# 20240709.net
KiCad netlist of a schematic drawn in EasyEDA Pro
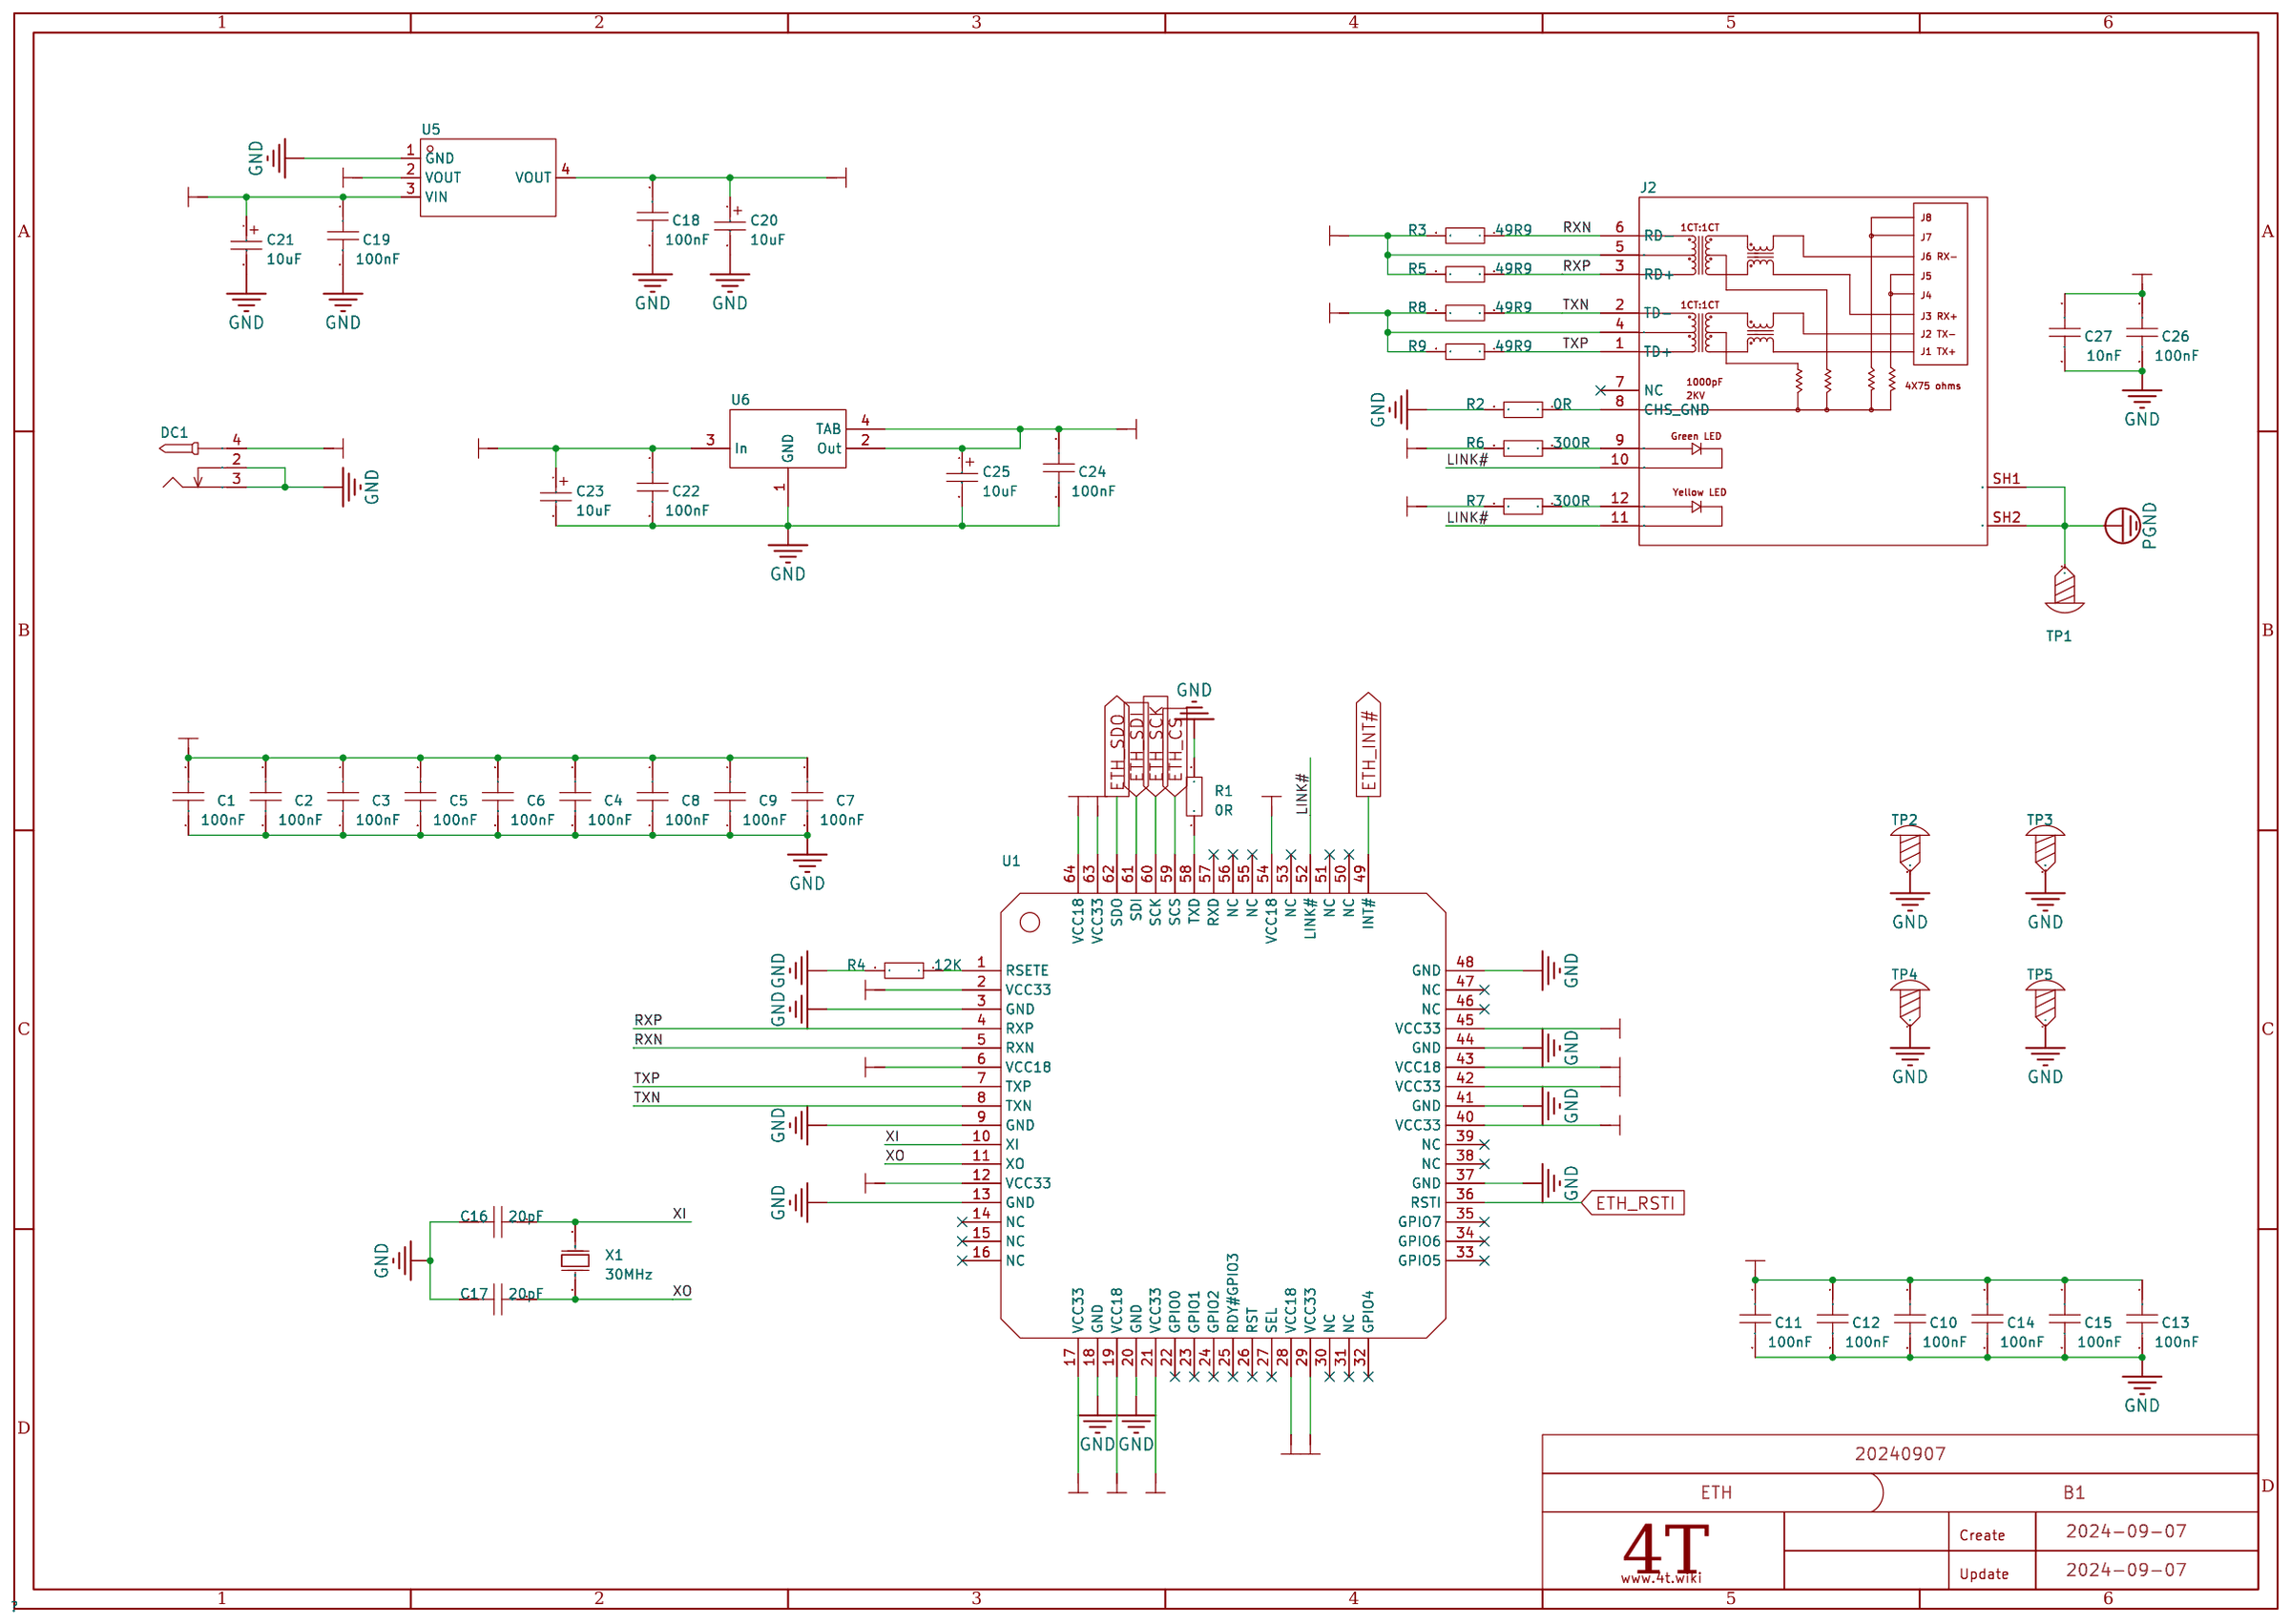
[diagram p0: ETH]
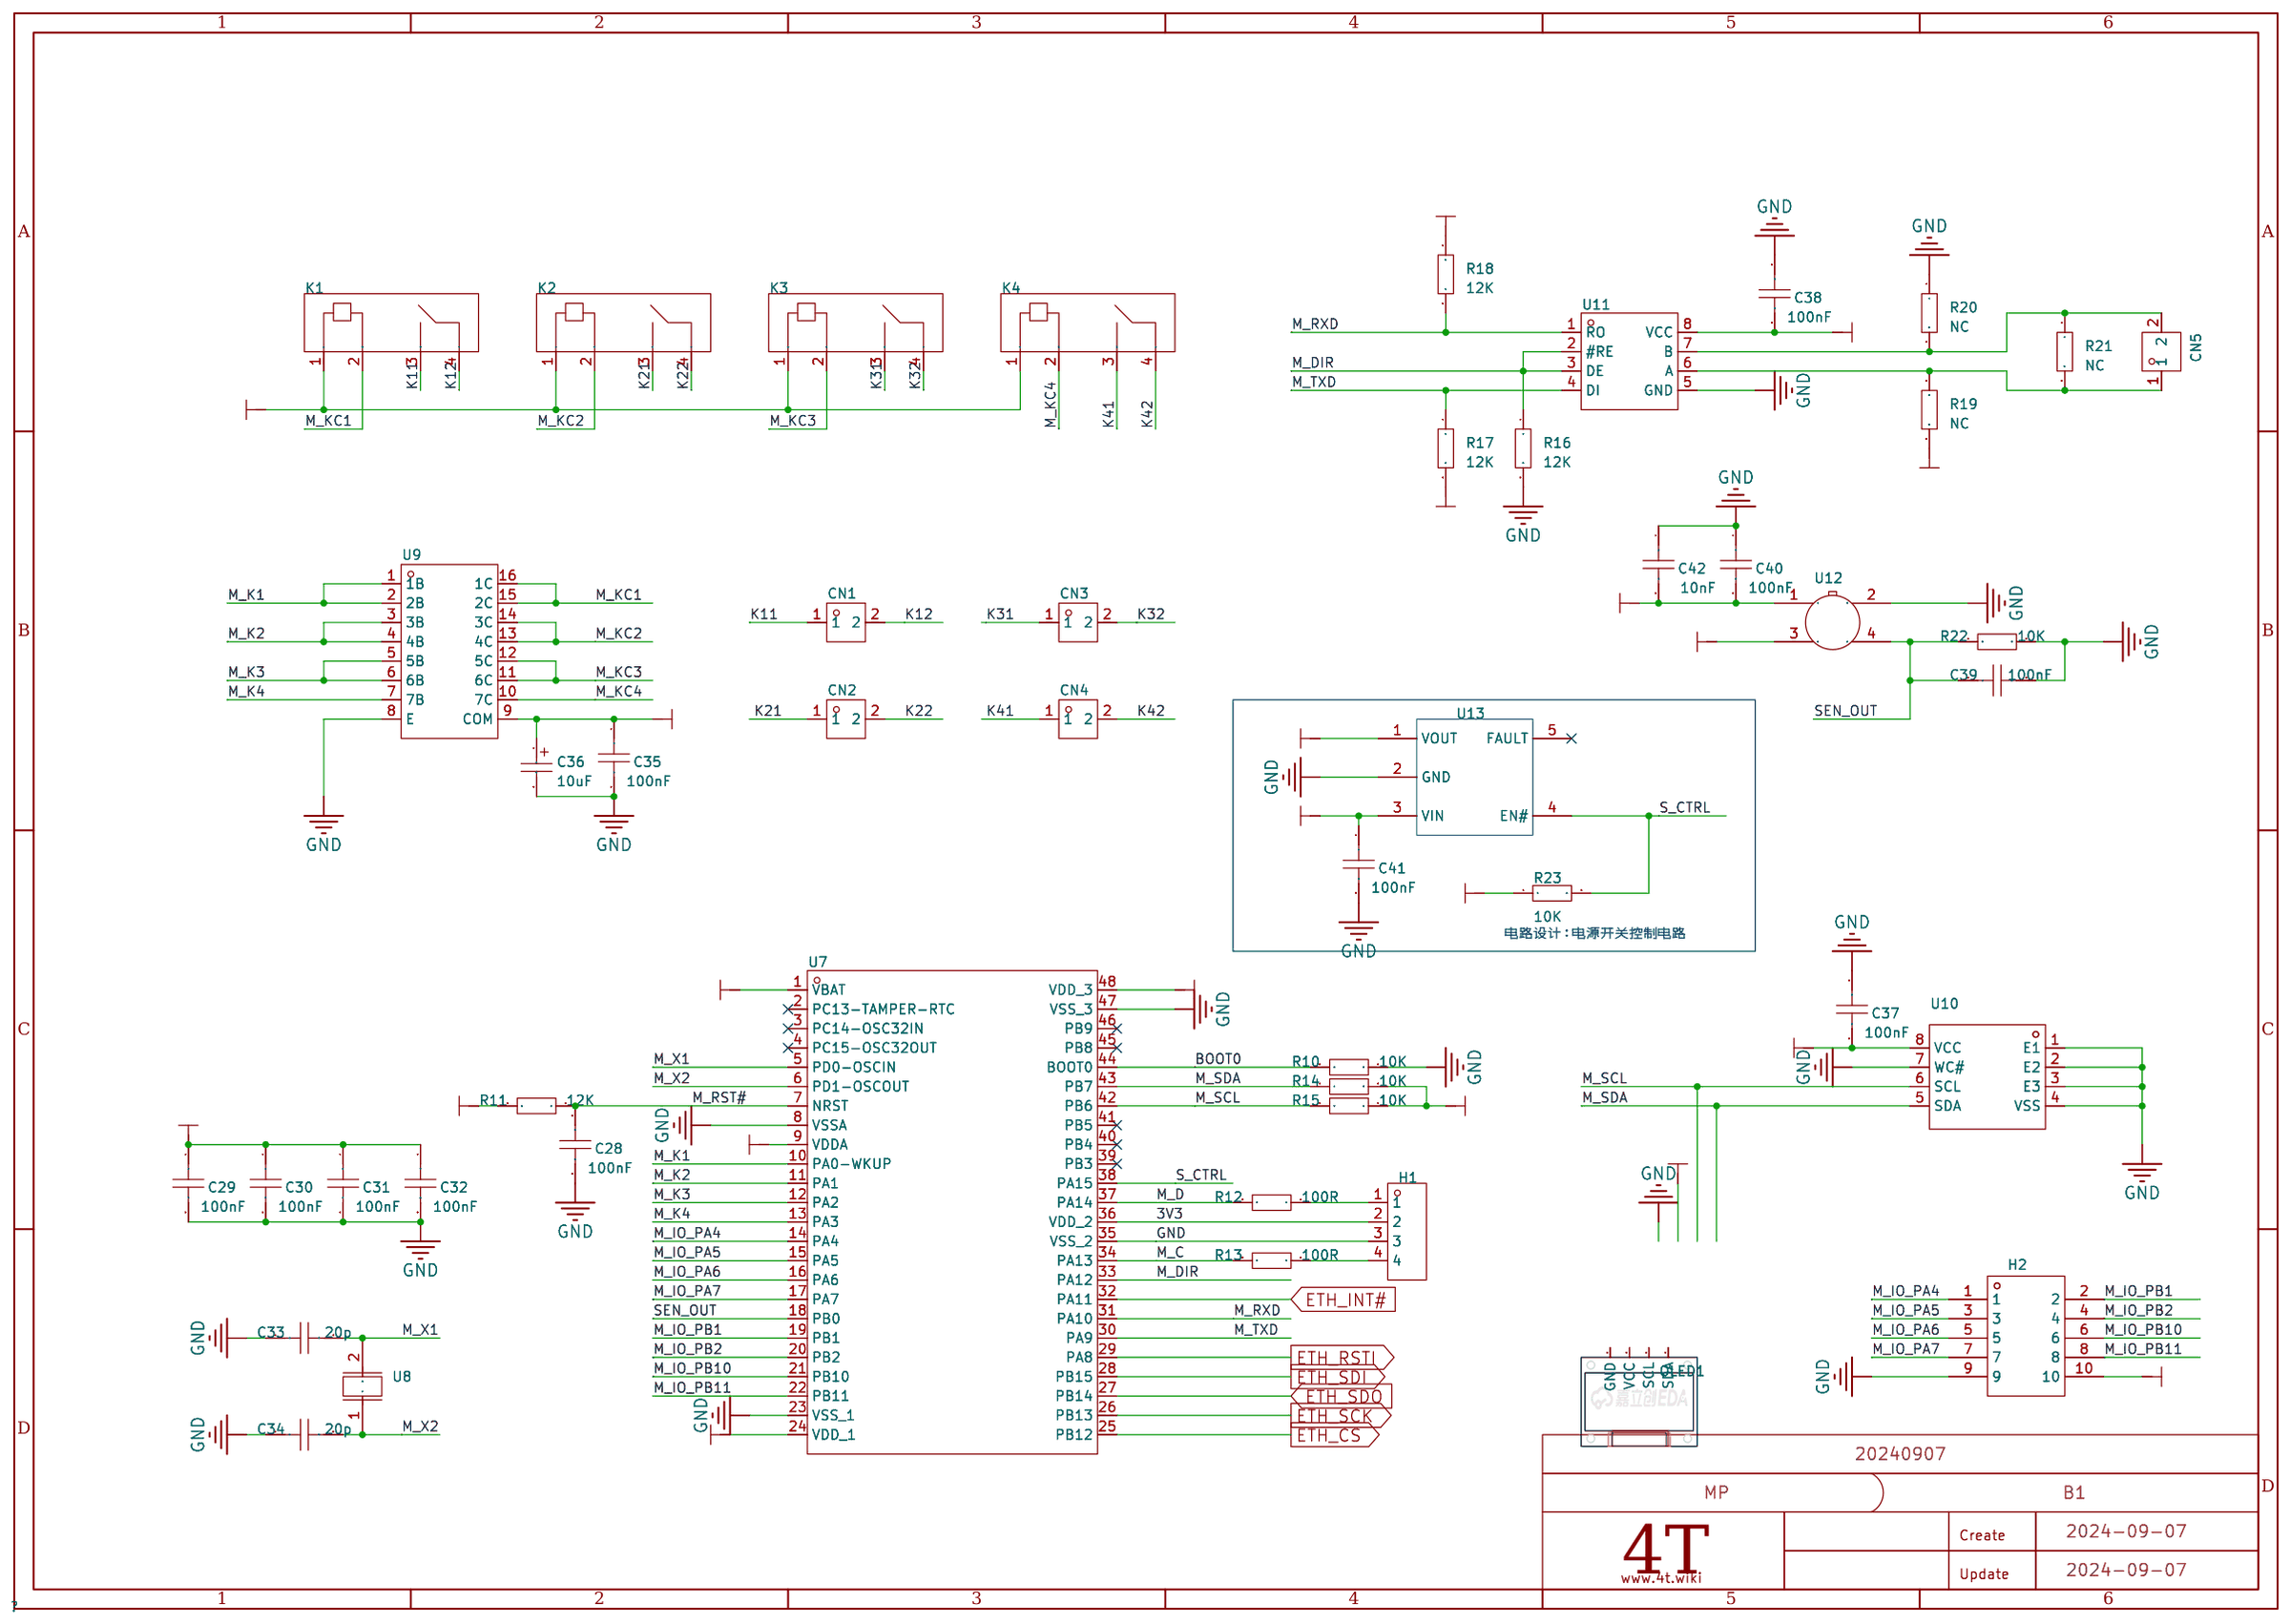
[diagram p1: MP]

(export (version "E")
  (design (tool "Eeschema 10.0.6"))
  (components
    (comp (ref "C1")
      (value "100nF")
      (footprint "easyedapro:C0805")
      (libsource (lib "easyedapro") (part "CapAcitance"))
    )
    (comp (ref "C2")
      (value "100nF")
      (footprint "easyedapro:C0805")
      (libsource (lib "easyedapro") (part "CapAcitance"))
    )
    (comp (ref "C3")
      (value "100nF")
      (footprint "easyedapro:C0805")
      (libsource (lib "easyedapro") (part "CapAcitance"))
    )
    (comp (ref "C4")
      (value "100nF")
      (footprint "easyedapro:C0805")
      (libsource (lib "easyedapro") (part "CapAcitance"))
    )
    (comp (ref "C5")
      (value "100nF")
      (footprint "easyedapro:C0805")
      (libsource (lib "easyedapro") (part "CapAcitance"))
    )
    (comp (ref "C6")
      (value "100nF")
      (footprint "easyedapro:C0805")
      (libsource (lib "easyedapro") (part "CapAcitance"))
    )
    (comp (ref "C7")
      (value "100nF")
      (footprint "easyedapro:C0805")
      (libsource (lib "easyedapro") (part "CapAcitance"))
    )
    (comp (ref "C8")
      (value "100nF")
      (footprint "easyedapro:C0805")
      (libsource (lib "easyedapro") (part "CapAcitance"))
    )
    (comp (ref "C9")
      (value "100nF")
      (footprint "easyedapro:C0805")
      (libsource (lib "easyedapro") (part "CapAcitance"))
    )
    (comp (ref "C10")
      (value "100nF")
      (footprint "easyedapro:C0805")
      (libsource (lib "easyedapro") (part "CapAcitance"))
    )
    (comp (ref "C11")
      (value "100nF")
      (footprint "easyedapro:C0805")
      (libsource (lib "easyedapro") (part "CapAcitance"))
    )
    (comp (ref "C12")
      (value "100nF")
      (footprint "easyedapro:C0805")
      (libsource (lib "easyedapro") (part "CapAcitance"))
    )
    (comp (ref "C13")
      (value "100nF")
      (footprint "easyedapro:C0805")
      (libsource (lib "easyedapro") (part "CapAcitance"))
    )
    (comp (ref "C14")
      (value "100nF")
      (footprint "easyedapro:C0805")
      (libsource (lib "easyedapro") (part "CapAcitance"))
    )
    (comp (ref "C15")
      (value "100nF")
      (footprint "easyedapro:C0805")
      (libsource (lib "easyedapro") (part "CapAcitance"))
    )
    (comp (ref "C16")
      (value "20pF")
      (footprint "easyedapro:C0805")
      (libsource (lib "easyedapro") (part "CapAcitance"))
    )
    (comp (ref "C17")
      (value "20pF")
      (footprint "easyedapro:C0805")
      (libsource (lib "easyedapro") (part "CapAcitance"))
    )
    (comp (ref "C18")
      (value "100nF")
      (footprint "easyedapro:C0805")
      (libsource (lib "easyedapro") (part "CapAcitance"))
    )
    (comp (ref "C19")
      (value "100nF")
      (footprint "easyedapro:C0805")
      (libsource (lib "easyedapro") (part "CapAcitance"))
    )
    (comp (ref "C20")
      (value "10uF")
      (footprint "easyedapro:C_Ele_SMD_3x5.4mm")
      (libsource (lib "easyedapro") (part "CAP"))
    )
    (comp (ref "C21")
      (value "10uF")
      (footprint "easyedapro:C_Ele_SMD_3x5.4mm")
      (libsource (lib "easyedapro") (part "CAP"))
    )
    (comp (ref "C22")
      (value "100nF")
      (footprint "easyedapro:C0805")
      (libsource (lib "easyedapro") (part "CapAcitance"))
    )
    (comp (ref "C23")
      (value "10uF")
      (footprint "easyedapro:C_Ele_SMD_3x5.4mm")
      (libsource (lib "easyedapro") (part "CAP"))
    )
    (comp (ref "C24")
      (value "100nF")
      (footprint "easyedapro:C0805")
      (libsource (lib "easyedapro") (part "CapAcitance"))
    )
    (comp (ref "C25")
      (value "10uF")
      (footprint "easyedapro:C_Ele_SMD_3x5.4mm")
      (libsource (lib "easyedapro") (part "CAP"))
    )
    (comp (ref "C26")
      (value "100nF")
      (footprint "easyedapro:C0805")
      (libsource (lib "easyedapro") (part "CapAcitance"))
    )
    (comp (ref "C27")
      (value "10nF")
      (footprint "easyedapro:C0805")
      (libsource (lib "easyedapro") (part "CapAcitance"))
    )
    (comp (ref "DC1")
      (value "~")
      (footprint "easyedapro:DC-2.0")
      (libsource (lib "easyedapro") (part "DC电源接口"))
    )
    (comp (ref "J2")
      (value "HY911105AE")
      (footprint "easyedapro:RJ45-TH_HR911105A")
      (description "连接器类型:RJ插座;USOC代码:RJ45;端口数量:1;等级:-;屏蔽:-;LED:-;")
      (fields (field (name "Manufacturer") "HANRUN(汉仁)"))
      (libsource (lib "easyedapro") (part "HY911105AE"))
    )
    (comp (ref "R1") (value "0R") (footprint "easyedapro:R0805") (libsource (lib "easyedapro") (part "电阻")))
    (comp (ref "R2") (value "0R") (footprint "easyedapro:R0805") (libsource (lib "easyedapro") (part "电阻")))
    (comp (ref "R3") (value "49R9") (footprint "easyedapro:R0805") (libsource (lib "easyedapro") (part "电阻")))
    (comp (ref "R4") (value "12K") (footprint "easyedapro:R0805") (libsource (lib "easyedapro") (part "电阻")))
    (comp (ref "R5") (value "49R9") (footprint "easyedapro:R0805") (libsource (lib "easyedapro") (part "电阻")))
    (comp (ref "R6") (value "300R") (footprint "easyedapro:R0805") (libsource (lib "easyedapro") (part "电阻")))
    (comp (ref "R7") (value "300R") (footprint "easyedapro:R0805") (libsource (lib "easyedapro") (part "电阻")))
    (comp (ref "R8") (value "49R9") (footprint "easyedapro:R0805") (libsource (lib "easyedapro") (part "电阻")))
    (comp (ref "R9") (value "49R9") (footprint "easyedapro:R0805") (libsource (lib "easyedapro") (part "电阻")))
    (comp (ref "TP1") (value "~") (footprint "easyedapro:M3螺丝") (libsource (lib "easyedapro") (part "螺丝孔")))
    (comp (ref "TP2") (value "~") (footprint "easyedapro:M3螺丝") (libsource (lib "easyedapro") (part "螺丝孔")))
    (comp (ref "TP3") (value "~") (footprint "easyedapro:M3螺丝") (libsource (lib "easyedapro") (part "螺丝孔")))
    (comp (ref "TP4") (value "~") (footprint "easyedapro:M3螺丝") (libsource (lib "easyedapro") (part "螺丝孔")))
    (comp (ref "TP5") (value "~") (footprint "easyedapro:M3螺丝") (libsource (lib "easyedapro") (part "螺丝孔")))
    (comp (ref "U1")
      (value "CH395Q")
      (footprint "easyedapro:LQFP-64_L10.0-W10.0-P0.50-LS12.0-BL")
      (description "应用功能:以太网控制器;通道数:-;接口类型:Parallel, SPI, UART;电源电压:1.65V~3.6V;电源电流:90mA;")
      (fields (field (name "Manufacturer") "WCH(南京沁恒)"))
      (libsource (lib "easyedapro") (part "CH395Q"))
    )
    (comp (ref "U5")
      (value "AMS1117-3.3")
      (footprint "easyedapro:SOT-223-3_L6.5-W3.4-P2.30-LS7.0-BR")
      (fields (field (name "Manufacturer") "AMS"))
      (libsource (lib "easyedapro") (part "AMS1117-3.3"))
    )
    (comp (ref "U6")
      (value "AMS1117-1.8")
      (footprint "easyedapro:SOT-223-4_L6.5-W3.5-P2.30-LS7.0-BR")
      (description "输出类型:固定;输出极性:正;输出通道数:1;最大输入电压:15V;输出电压:1.8V~1.8V;压差:1.3V@(1A);输出电流:1A;电源纹波抑制比(PSRR):75dB@(120Hz);")
      (fields (field (name "Manufacturer") "AMS"))
      (libsource (lib "easyedapro") (part "AMS1117-1.8"))
    )
    (comp (ref "X1")
      (value "30MHz")
      (footprint "easyedapro:OSC-SMD_L5.0-W3.2")
      (description "晶振类型:贴片无源晶振;频率:30MHz;频率公差:±10ppm;频率稳定度:±50ppm;负载电容:20pF;工作温度:-40°C~+85°C;")
      (fields (field (name "Manufacturer Part") "X503230MSB2GI") (field (name "Manufacturer") "YXC(扬兴晶振)"))
      (libsource (lib "easyedapro") (part "X503230MSB2GI"))
    )
    (comp (ref "C28")
      (value "100nF")
      (footprint "easyedapro:C0805")
      (libsource (lib "easyedapro") (part "CapAcitance"))
    )
    (comp (ref "C29")
      (value "100nF")
      (footprint "easyedapro:C0805")
      (libsource (lib "easyedapro") (part "CapAcitance"))
    )
    (comp (ref "C30")
      (value "100nF")
      (footprint "easyedapro:C0805")
      (libsource (lib "easyedapro") (part "CapAcitance"))
    )
    (comp (ref "C31")
      (value "100nF")
      (footprint "easyedapro:C0805")
      (libsource (lib "easyedapro") (part "CapAcitance"))
    )
    (comp (ref "C32")
      (value "100nF")
      (footprint "easyedapro:C0805")
      (libsource (lib "easyedapro") (part "CapAcitance"))
    )
    (comp (ref "C33")
      (value "20p")
      (footprint "easyedapro:C0805")
      (libsource (lib "easyedapro") (part "CapAcitance"))
    )
    (comp (ref "C34")
      (value "20p")
      (footprint "easyedapro:C0805")
      (libsource (lib "easyedapro") (part "CapAcitance"))
    )
    (comp (ref "C35")
      (value "100nF")
      (footprint "easyedapro:C0805")
      (libsource (lib "easyedapro") (part "CapAcitance"))
    )
    (comp (ref "C36")
      (value "10uF")
      (footprint "easyedapro:C_Ele_SMD_3x5.4mm")
      (libsource (lib "easyedapro") (part "CAP"))
    )
    (comp (ref "C37")
      (value "100nF")
      (footprint "easyedapro:C0805")
      (libsource (lib "easyedapro") (part "CapAcitance"))
    )
    (comp (ref "C38")
      (value "100nF")
      (footprint "easyedapro:C0805")
      (libsource (lib "easyedapro") (part "CapAcitance"))
    )
    (comp (ref "C39")
      (value "100nF")
      (footprint "easyedapro:C0805")
      (libsource (lib "easyedapro") (part "CapAcitance"))
    )
    (comp (ref "C40")
      (value "100nF")
      (footprint "easyedapro:C0805")
      (libsource (lib "easyedapro") (part "CapAcitance"))
    )
    (comp (ref "C41")
      (value "100nF")
      (footprint "easyedapro:C0805")
      (libsource (lib "easyedapro") (part "CapAcitance"))
    )
    (comp (ref "C42")
      (value "10nF")
      (footprint "easyedapro:C0805")
      (libsource (lib "easyedapro") (part "CapAcitance"))
    )
    (comp (ref "CN1")
      (value "KF128L-5.08-2P 蓝色")
      (footprint "easyedapro:TH_KF128L-5.08-2P")
      (libsource (lib "easyedapro") (part "KF128L-5.08-2P 蓝色"))
    )
    (comp (ref "CN2")
      (value "KF128L-5.08-2P 蓝色")
      (footprint "easyedapro:TH_KF128L-5.08-2P")
      (libsource (lib "easyedapro") (part "KF128L-5.08-2P 蓝色"))
    )
    (comp (ref "CN3")
      (value "KF128L-5.08-2P 蓝色")
      (footprint "easyedapro:TH_KF128L-5.08-2P")
      (libsource (lib "easyedapro") (part "KF128L-5.08-2P 蓝色"))
    )
    (comp (ref "CN4")
      (value "KF128L-5.08-2P 蓝色")
      (footprint "easyedapro:TH_KF128L-5.08-2P")
      (libsource (lib "easyedapro") (part "KF128L-5.08-2P 蓝色"))
    )
    (comp (ref "CN5")
      (value "KF128L-5.08-2P 蓝色")
      (footprint "easyedapro:TH_KF128L-5.08-2P")
      (libsource (lib "easyedapro") (part "KF128L-5.08-2P 蓝色"))
    )
    (comp (ref "H1")
      (value "~")
      (footprint "easyedapro:HDR-TH_4P-P2.54-V-F")
      (libsource (lib "easyedapro") (part "2.54-1*4P母"))
    )
    (comp (ref "H2")
      (value "~")
      (footprint "easyedapro:HDR-TH_10P-P2.54-V-M-R2-C5-S2.54")
      (libsource (lib "easyedapro") (part "HDR-M-2.54_2x5"))
    )
    (comp (ref "K1")
      (value "HF49FD/012-1H12")
      (footprint "easyedapro:RELAY-TH_HF49FD-XXX-1H12-XXX")
      (description "线圈电压:12V;线圈类型:非极化-单线圈;触点形式:一组常开:1A(单刀单掷-常开);最大切换电流:5A;触点材料:AgNi;")
      (fields (field (name "Manufacturer") "HF(宏发)"))
      (libsource (lib "easyedapro") (part "HF49FD/012-1H12"))
    )
    (comp (ref "K2")
      (value "HF49FD/012-1H12")
      (footprint "easyedapro:RELAY-TH_HF49FD-XXX-1H12-XXX")
      (description "线圈电压:12V;线圈类型:非极化-单线圈;触点形式:一组常开:1A(单刀单掷-常开);最大切换电流:5A;触点材料:AgNi;")
      (fields (field (name "Manufacturer") "HF(宏发)"))
      (libsource (lib "easyedapro") (part "HF49FD/012-1H12"))
    )
    (comp (ref "K3")
      (value "HF49FD/012-1H12")
      (footprint "easyedapro:RELAY-TH_HF49FD-XXX-1H12-XXX")
      (description "线圈电压:12V;线圈类型:非极化-单线圈;触点形式:一组常开:1A(单刀单掷-常开);最大切换电流:5A;触点材料:AgNi;")
      (fields (field (name "Manufacturer") "HF(宏发)"))
      (libsource (lib "easyedapro") (part "HF49FD/012-1H12"))
    )
    (comp (ref "K4")
      (value "HF49FD/012-1H12")
      (footprint "easyedapro:RELAY-TH_HF49FD-XXX-1H12-XXX")
      (description "线圈电压:12V;线圈类型:非极化-单线圈;触点形式:一组常开:1A(单刀单掷-常开);最大切换电流:5A;触点材料:AgNi;")
      (fields (field (name "Manufacturer") "HF(宏发)"))
      (libsource (lib "easyedapro") (part "HF49FD/012-1H12"))
    )
    (comp (ref "OLED1")
      (value "~")
      (footprint "easyedapro:0.96OLED_4P")
      (libsource (lib "easyedapro") (part "0.96OLED模块_4P"))
    )
    (comp (ref "R10") (value "10K") (footprint "easyedapro:R0805") (libsource (lib "easyedapro") (part "电阻")))
    (comp (ref "R11") (value "12K") (footprint "easyedapro:R0805") (libsource (lib "easyedapro") (part "电阻")))
    (comp (ref "R12")
      (value "100R")
      (footprint "easyedapro:R0805")
      (libsource (lib "easyedapro") (part "电阻"))
    )
    (comp (ref "R13")
      (value "100R")
      (footprint "easyedapro:R0805")
      (libsource (lib "easyedapro") (part "电阻"))
    )
    (comp (ref "R14") (value "10K") (footprint "easyedapro:R0805") (libsource (lib "easyedapro") (part "电阻")))
    (comp (ref "R15") (value "10K") (footprint "easyedapro:R0805") (libsource (lib "easyedapro") (part "电阻")))
    (comp (ref "R16") (value "12K") (footprint "easyedapro:R0805") (libsource (lib "easyedapro") (part "电阻")))
    (comp (ref "R17") (value "12K") (footprint "easyedapro:R0805") (libsource (lib "easyedapro") (part "电阻")))
    (comp (ref "R18") (value "12K") (footprint "easyedapro:R0805") (libsource (lib "easyedapro") (part "电阻")))
    (comp (ref "R19") (value "NC") (footprint "easyedapro:R0805") (libsource (lib "easyedapro") (part "电阻")))
    (comp (ref "R20") (value "NC") (footprint "easyedapro:R0805") (libsource (lib "easyedapro") (part "电阻")))
    (comp (ref "R21") (value "NC") (footprint "easyedapro:R0805") (libsource (lib "easyedapro") (part "电阻")))
    (comp (ref "R22") (value "10K") (footprint "easyedapro:R0805") (libsource (lib "easyedapro") (part "电阻")))
    (comp (ref "R23") (value "10K") (footprint "easyedapro:R0805") (libsource (lib "easyedapro") (part "电阻")))
    (comp (ref "U7")
      (value "GD32F303CBT6")
      (footprint "easyedapro:LQFP-48_L7.0-W7.0-P0.50-LS9.0-BL")
      (fields (field (name "Manufacturer") "GigaDevice(兆易创新)"))
      (libsource (lib "easyedapro") (part "GD32F303CBT6"))
    )
    (comp (ref "U8")
      (value "8M-5032-2P")
      (footprint "easyedapro:CRYSTAL-SMD_L5.0-W3.2")
      (libsource (lib "easyedapro") (part "8M-5032-2P"))
    )
    (comp (ref "U9")
      (value "ULN2003")
      (footprint "easyedapro:SOIC-16_L9.9-W3.9-P1.27-LS6.0-BL")
      (fields (field (name "Manufacturer") "IDCHIP(英锐芯)"))
      (libsource (lib "easyedapro") (part "ULN2003_C688859"))
    )
    (comp (ref "U10")
      (value "M24C02-WMN6TP")
      (footprint "easyedapro:SOIC-8_L4.9-W3.9-P1.27-LS6.0-BL")
      (description "2-Kbit(256 x 8bit)，I2C接口，工作电压：2.5V to 5.5V")
      (fields (field (name "Manufacturer") "ST(意法半导体)"))
      (libsource (lib "easyedapro") (part "M24C02-WMN6TP"))
    )
    (comp (ref "U11")
      (value "MAX3485ESA")
      (footprint "easyedapro:SOP-8_L5.0-W4.0-P1.27-LS6.0-BL")
      (fields (field (name "Manufacturer") "UMW(广东友台半导体)"))
      (libsource (lib "easyedapro") (part "MAX3485ESA"))
    )
    (comp (ref "U12")
      (value "MP-2")
      (footprint "easyedapro:SENSOR-TH_MP-5")
      (fields (field (name "Manufacturer") "Winsen(炜盛)"))
      (libsource (lib "easyedapro") (part "MP-2"))
    )
    (comp (ref "U13")
      (value "~")
      (footprint "easyedapro:SOT_PDS")
      (libsource (lib "easyedapro") (part "PDS"))
    )
  )
  (nets
    (net (code "1") (name "1V8") (class "Default")
      (node (ref "C10") (pin "1") (pinfunction "1_1") (pintype "input"))
      (node (ref "C11") (pin "1") (pinfunction "1_1") (pintype "input"))
      (node (ref "C12") (pin "1") (pinfunction "1_1") (pintype "input"))
      (node (ref "C13") (pin "1") (pinfunction "1_1") (pintype "input"))
      (node (ref "C14") (pin "1") (pinfunction "1_1") (pintype "input"))
      (node (ref "C15") (pin "1") (pinfunction "1_1") (pintype "input"))
      (node (ref "C24") (pin "1") (pinfunction "1_1") (pintype "input"))
      (node (ref "C25") (pin "1") (pinfunction "1_1") (pintype "input"))
      (node (ref "U1") (pin "19") (pinfunction "VCC18_19") (pintype "input"))
      (node (ref "U1") (pin "28") (pinfunction "VCC18_28") (pintype "input"))
      (node (ref "U1") (pin "43") (pinfunction "VCC18_43") (pintype "input"))
      (node (ref "U1") (pin "54") (pinfunction "VCC18_54") (pintype "input"))
      (node (ref "U1") (pin "6") (pinfunction "VCC18_6") (pintype "input"))
      (node (ref "U1") (pin "63") (pinfunction "VCC33_63") (pintype "input"))
      (node (ref "U6") (pin "2") (pinfunction "Out_2") (pintype "input"))
      (node (ref "U6") (pin "4") (pinfunction "TAB_4") (pintype "input"))
    )
    (net (code "2") (name "3V3") (class "Default")
      (node (ref "C1") (pin "1") (pinfunction "1_1") (pintype "input"))
      (node (ref "C18") (pin "1") (pinfunction "1_1") (pintype "input"))
      (node (ref "C2") (pin "1") (pinfunction "1_1") (pintype "input"))
      (node (ref "C20") (pin "1") (pinfunction "1_1") (pintype "input"))
      (node (ref "C22") (pin "1") (pinfunction "1_1") (pintype "input"))
      (node (ref "C23") (pin "1") (pinfunction "1_1") (pintype "input"))
      (node (ref "C26") (pin "1") (pinfunction "1_1") (pintype "input"))
      (node (ref "C27") (pin "1") (pinfunction "1_1") (pintype "input"))
      (node (ref "C29") (pin "1") (pinfunction "1_1") (pintype "input"))
      (node (ref "C3") (pin "1") (pinfunction "1_1") (pintype "input"))
      (node (ref "C30") (pin "1") (pinfunction "1_1") (pintype "input"))
      (node (ref "C31") (pin "1") (pinfunction "1_1") (pintype "input"))
      (node (ref "C32") (pin "1") (pinfunction "1_1") (pintype "input"))
      (node (ref "C37") (pin "2") (pinfunction "2_2") (pintype "input"))
      (node (ref "C38") (pin "2") (pinfunction "2_2") (pintype "input"))
      (node (ref "C4") (pin "1") (pinfunction "1_1") (pintype "input"))
      (node (ref "C5") (pin "1") (pinfunction "1_1") (pintype "input"))
      (node (ref "C6") (pin "1") (pinfunction "1_1") (pintype "input"))
      (node (ref "C7") (pin "1") (pinfunction "1_1") (pintype "input"))
      (node (ref "C8") (pin "1") (pinfunction "1_1") (pintype "input"))
      (node (ref "C9") (pin "1") (pinfunction "1_1") (pintype "input"))
      (node (ref "H1") (pin "2") (pinfunction "2_2") (pintype "input"))
      (node (ref "H2") (pin "10") (pinfunction "10_10") (pintype "input"))
      (node (ref "J2") (pin "4") (pinfunction "4_4") (pintype "input"))
      (node (ref "J2") (pin "5") (pinfunction "5_5") (pintype "input"))
      (node (ref "R11") (pin "2") (pinfunction "2_2") (pintype "input"))
      (node (ref "R14") (pin "2") (pinfunction "2_2") (pintype "input"))
      (node (ref "R15") (pin "1") (pinfunction "1_1") (pintype "input"))
      (node (ref "R17") (pin "2") (pinfunction "2_2") (pintype "input"))
      (node (ref "R18") (pin "1") (pinfunction "1_1") (pintype "input"))
      (node (ref "R19") (pin "2") (pinfunction "2_2") (pintype "input"))
      (node (ref "R23") (pin "1") (pinfunction "1_1") (pintype "input"))
      (node (ref "R3") (pin "2") (pinfunction "2_2") (pintype "input"))
      (node (ref "R5") (pin "2") (pinfunction "2_2") (pintype "input"))
      (node (ref "R6") (pin "2") (pinfunction "2_2") (pintype "input"))
      (node (ref "R7") (pin "2") (pinfunction "2_2") (pintype "input"))
      (node (ref "R8") (pin "2") (pinfunction "2_2") (pintype "input"))
      (node (ref "R9") (pin "2") (pinfunction "2_2") (pintype "input"))
      (node (ref "U1") (pin "12") (pinfunction "VCC33_12") (pintype "input"))
      (node (ref "U1") (pin "17") (pinfunction "VCC33_17") (pintype "input"))
      (node (ref "U1") (pin "2") (pinfunction "VCC33_2") (pintype "input"))
      (node (ref "U1") (pin "21") (pinfunction "VCC33_21") (pintype "input"))
      (node (ref "U1") (pin "29") (pinfunction "VCC33_29") (pintype "input"))
      (node (ref "U1") (pin "40") (pinfunction "VCC33_40") (pintype "input"))
      (node (ref "U1") (pin "42") (pinfunction "VCC33_42") (pintype "input"))
      (node (ref "U1") (pin "45") (pinfunction "VCC33_45") (pintype "input"))
      (node (ref "U1") (pin "64") (pinfunction "VCC18_64") (pintype "input"))
      (node (ref "U10") (pin "8") (pinfunction "VCC_8") (pintype "input"))
      (node (ref "U11") (pin "8") (pinfunction "VCC_8") (pintype "input"))
      (node (ref "U12") (pin "3") (pinfunction "3_3") (pintype "input"))
      (node (ref "U5") (pin "2") (pinfunction "VOUT_2") (pintype "input"))
      (node (ref "U5") (pin "4") (pinfunction "VOUT_4") (pintype "input"))
      (node (ref "U6") (pin "3") (pinfunction "In_3") (pintype "input"))
      (node (ref "U7") (pin "1") (pinfunction "VBAT_1") (pintype "input"))
      (node (ref "U7") (pin "24") (pinfunction "VDD_1_24") (pintype "input"))
      (node (ref "U7") (pin "36") (pinfunction "VDD_2_36") (pintype "input"))
      (node (ref "U7") (pin "48") (pinfunction "VDD_3_48") (pintype "input"))
      (node (ref "U7") (pin "9") (pinfunction "VDDA_9") (pintype "input"))
    )
    (net (code "3") (name "BOOT0") (class "Default")
      (node (ref "R10") (pin "2") (pinfunction "2_2") (pintype "input"))
      (node (ref "U7") (pin "44") (pinfunction "BOOT0_44") (pintype "input"))
    )
    (net (code "4") (name "DC") (class "Default")
      (node (ref "C19") (pin "1") (pinfunction "1_1") (pintype "input"))
      (node (ref "C21") (pin "1") (pinfunction "1_1") (pintype "input"))
      (node (ref "C35") (pin "1") (pinfunction "1_1") (pintype "input"))
      (node (ref "C36") (pin "1") (pinfunction "1_1") (pintype "input"))
      (node (ref "C41") (pin "1") (pinfunction "1_1") (pintype "input"))
      (node (ref "DC1") (pin "4") (pinfunction "4_4") (pintype "input"))
      (node (ref "K1") (pin "1") (pinfunction "1_1") (pintype "input"))
      (node (ref "K2") (pin "1") (pinfunction "1_1") (pintype "input"))
      (node (ref "K3") (pin "1") (pinfunction "1_1") (pintype "input"))
      (node (ref "K4") (pin "1") (pinfunction "1_1") (pintype "input"))
      (node (ref "U13") (pin "3") (pinfunction "VIN_3") (pintype "input"))
      (node (ref "U5") (pin "3") (pinfunction "VIN_3") (pintype "input"))
      (node (ref "U9") (pin "9") (pinfunction "COM_9") (pintype "input"))
    )
    (net (code "5") (name "ETH_CS") (class "Default")
      (node (ref "U1") (pin "59") (pinfunction "SCS_59") (pintype "input"))
      (node (ref "U7") (pin "25") (pinfunction "PB12_25") (pintype "input"))
    )
    (net (code "6") (name "ETH_INT#") (class "Default")
      (node (ref "U1") (pin "49") (pinfunction "INT#_49") (pintype "input"))
      (node (ref "U7") (pin "32") (pinfunction "PA11_32") (pintype "input"))
    )
    (net (code "7") (name "ETH_RSTI") (class "Default")
      (node (ref "U1") (pin "36") (pinfunction "RSTI_36") (pintype "input"))
      (node (ref "U7") (pin "29") (pinfunction "PA8_29") (pintype "input"))
    )
    (net (code "8") (name "ETH_SCK") (class "Default")
      (node (ref "U1") (pin "60") (pinfunction "SCK_60") (pintype "input"))
      (node (ref "U7") (pin "26") (pinfunction "PB13_26") (pintype "input"))
    )
    (net (code "9") (name "ETH_SDI") (class "Default")
      (node (ref "U1") (pin "61") (pinfunction "SDI_61") (pintype "input"))
      (node (ref "U7") (pin "28") (pinfunction "PB15_28") (pintype "input"))
    )
    (net (code "10") (name "ETH_SDO") (class "Default")
      (node (ref "U1") (pin "62") (pinfunction "SDO_62") (pintype "input"))
      (node (ref "U7") (pin "27") (pinfunction "PB14_27") (pintype "input"))
    )
    (net (code "11") (name "GND") (class "Default")
      (node (ref "C1") (pin "2") (pinfunction "2_2") (pintype "input"))
      (node (ref "C10") (pin "2") (pinfunction "2_2") (pintype "input"))
      (node (ref "C11") (pin "2") (pinfunction "2_2") (pintype "input"))
      (node (ref "C12") (pin "2") (pinfunction "2_2") (pintype "input"))
      (node (ref "C13") (pin "2") (pinfunction "2_2") (pintype "input"))
      (node (ref "C14") (pin "2") (pinfunction "2_2") (pintype "input"))
      (node (ref "C15") (pin "2") (pinfunction "2_2") (pintype "input"))
      (node (ref "C16") (pin "1") (pinfunction "1_1") (pintype "input"))
      (node (ref "C17") (pin "1") (pinfunction "1_1") (pintype "input"))
      (node (ref "C18") (pin "2") (pinfunction "2_2") (pintype "input"))
      (node (ref "C19") (pin "2") (pinfunction "2_2") (pintype "input"))
      (node (ref "C2") (pin "2") (pinfunction "2_2") (pintype "input"))
      (node (ref "C20") (pin "2") (pinfunction "2_2") (pintype "input"))
      (node (ref "C21") (pin "2") (pinfunction "2_2") (pintype "input"))
      (node (ref "C22") (pin "2") (pinfunction "2_2") (pintype "input"))
      (node (ref "C23") (pin "2") (pinfunction "2_2") (pintype "input"))
      (node (ref "C24") (pin "2") (pinfunction "2_2") (pintype "input"))
      (node (ref "C25") (pin "2") (pinfunction "2_2") (pintype "input"))
      (node (ref "C26") (pin "2") (pinfunction "2_2") (pintype "input"))
      (node (ref "C27") (pin "2") (pinfunction "2_2") (pintype "input"))
      (node (ref "C28") (pin "2") (pinfunction "2_2") (pintype "input"))
      (node (ref "C29") (pin "2") (pinfunction "2_2") (pintype "input"))
      (node (ref "C3") (pin "2") (pinfunction "2_2") (pintype "input"))
      (node (ref "C30") (pin "2") (pinfunction "2_2") (pintype "input"))
      (node (ref "C31") (pin "2") (pinfunction "2_2") (pintype "input"))
      (node (ref "C32") (pin "2") (pinfunction "2_2") (pintype "input"))
      (node (ref "C33") (pin "1") (pinfunction "1_1") (pintype "input"))
      (node (ref "C34") (pin "1") (pinfunction "1_1") (pintype "input"))
      (node (ref "C35") (pin "2") (pinfunction "2_2") (pintype "input"))
      (node (ref "C36") (pin "2") (pinfunction "2_2") (pintype "input"))
      (node (ref "C37") (pin "1") (pinfunction "1_1") (pintype "input"))
      (node (ref "C38") (pin "1") (pinfunction "1_1") (pintype "input"))
      (node (ref "C39") (pin "2") (pinfunction "2_2") (pintype "input"))
      (node (ref "C4") (pin "2") (pinfunction "2_2") (pintype "input"))
      (node (ref "C40") (pin "1") (pinfunction "1_1") (pintype "input"))
      (node (ref "C41") (pin "2") (pinfunction "2_2") (pintype "input"))
      (node (ref "C42") (pin "1") (pinfunction "1_1") (pintype "input"))
      (node (ref "C5") (pin "2") (pinfunction "2_2") (pintype "input"))
      (node (ref "C6") (pin "2") (pinfunction "2_2") (pintype "input"))
      (node (ref "C7") (pin "2") (pinfunction "2_2") (pintype "input"))
      (node (ref "C8") (pin "2") (pinfunction "2_2") (pintype "input"))
      (node (ref "C9") (pin "2") (pinfunction "2_2") (pintype "input"))
      (node (ref "DC1") (pin "2") (pinfunction "2_2") (pintype "input"))
      (node (ref "DC1") (pin "3") (pinfunction "3_3") (pintype "input"))
      (node (ref "H1") (pin "3") (pinfunction "3_3") (pintype "input"))
      (node (ref "H2") (pin "9") (pinfunction "9_9") (pintype "input"))
      (node (ref "R1") (pin "2") (pinfunction "2_2") (pintype "input"))
      (node (ref "R10") (pin "1") (pinfunction "1_1") (pintype "input"))
      (node (ref "R16") (pin "2") (pinfunction "2_2") (pintype "input"))
      (node (ref "R2") (pin "2") (pinfunction "2_2") (pintype "input"))
      (node (ref "R20") (pin "1") (pinfunction "1_1") (pintype "input"))
      (node (ref "R22") (pin "2") (pinfunction "2_2") (pintype "input"))
      (node (ref "R4") (pin "2") (pinfunction "2_2") (pintype "input"))
      (node (ref "TP2") (pin "1") (pinfunction "1_1") (pintype "input"))
      (node (ref "TP3") (pin "1") (pinfunction "1_1") (pintype "input"))
      (node (ref "TP4") (pin "1") (pinfunction "1_1") (pintype "input"))
      (node (ref "TP5") (pin "1") (pinfunction "1_1") (pintype "input"))
      (node (ref "U1") (pin "13") (pinfunction "GND_13") (pintype "input"))
      (node (ref "U1") (pin "18") (pinfunction "GND_18") (pintype "input"))
      (node (ref "U1") (pin "20") (pinfunction "GND_20") (pintype "input"))
      (node (ref "U1") (pin "3") (pinfunction "GND_3") (pintype "input"))
      (node (ref "U1") (pin "37") (pinfunction "GND_37") (pintype "input"))
      (node (ref "U1") (pin "41") (pinfunction "GND_41") (pintype "input"))
      (node (ref "U1") (pin "44") (pinfunction "GND_44") (pintype "input"))
      (node (ref "U1") (pin "48") (pinfunction "GND_48") (pintype "input"))
      (node (ref "U1") (pin "9") (pinfunction "GND_9") (pintype "input"))
      (node (ref "U10") (pin "1") (pinfunction "E1_1") (pintype "input"))
      (node (ref "U10") (pin "2") (pinfunction "E2_2") (pintype "input"))
      (node (ref "U10") (pin "3") (pinfunction "E3_3") (pintype "input"))
      (node (ref "U10") (pin "4") (pinfunction "VSS_4") (pintype "input"))
      (node (ref "U10") (pin "7") (pinfunction "WC#_7") (pintype "input"))
      (node (ref "U11") (pin "5") (pinfunction "GND_5") (pintype "input"))
      (node (ref "U12") (pin "2") (pinfunction "2_2") (pintype "input"))
      (node (ref "U13") (pin "2") (pinfunction "GND_2") (pintype "input"))
      (node (ref "U5") (pin "1") (pinfunction "GND_1") (pintype "input"))
      (node (ref "U6") (pin "1") (pinfunction "GND_1") (pintype "input"))
      (node (ref "U7") (pin "23") (pinfunction "VSS_1_23") (pintype "input"))
      (node (ref "U7") (pin "35") (pinfunction "VSS_2_35") (pintype "input"))
      (node (ref "U7") (pin "47") (pinfunction "VSS_3_47") (pintype "input"))
      (node (ref "U7") (pin "8") (pinfunction "VSSA_8") (pintype "input"))
      (node (ref "U9") (pin "8") (pinfunction "E_8") (pintype "input"))
    )
    (net (code "12") (name "K11") (class "Default")
      (node (ref "CN1") (pin "1") (pinfunction "1_1") (pintype "input"))
      (node (ref "K1") (pin "3") (pinfunction "3_3") (pintype "input"))
    )
    (net (code "13") (name "K12") (class "Default")
      (node (ref "CN1") (pin "2") (pinfunction "2_2") (pintype "input"))
      (node (ref "K1") (pin "4") (pinfunction "4_4") (pintype "input"))
    )
    (net (code "14") (name "K21") (class "Default")
      (node (ref "CN2") (pin "1") (pinfunction "1_1") (pintype "input"))
      (node (ref "K2") (pin "3") (pinfunction "3_3") (pintype "input"))
    )
    (net (code "15") (name "K22") (class "Default")
      (node (ref "CN2") (pin "2") (pinfunction "2_2") (pintype "input"))
      (node (ref "K2") (pin "4") (pinfunction "4_4") (pintype "input"))
    )
    (net (code "16") (name "K31") (class "Default")
      (node (ref "CN3") (pin "1") (pinfunction "1_1") (pintype "input"))
      (node (ref "K3") (pin "3") (pinfunction "3_3") (pintype "input"))
    )
    (net (code "17") (name "K32") (class "Default")
      (node (ref "CN3") (pin "2") (pinfunction "2_2") (pintype "input"))
      (node (ref "K3") (pin "4") (pinfunction "4_4") (pintype "input"))
    )
    (net (code "18") (name "K41") (class "Default")
      (node (ref "CN4") (pin "1") (pinfunction "1_1") (pintype "input"))
      (node (ref "K4") (pin "3") (pinfunction "3_3") (pintype "input"))
    )
    (net (code "19") (name "K42") (class "Default")
      (node (ref "CN4") (pin "2") (pinfunction "2_2") (pintype "input"))
      (node (ref "K4") (pin "4") (pinfunction "4_4") (pintype "input"))
    )
    (net (code "20") (name "LINK#") (class "Default")
      (node (ref "J2") (pin "10") (pinfunction "10_10") (pintype "input"))
      (node (ref "J2") (pin "11") (pinfunction "11_11") (pintype "input"))
      (node (ref "U1") (pin "52") (pinfunction "LINK#_52") (pintype "input"))
    )
    (net (code "21") (name "M_C") (class "Default")
      (node (ref "R13") (pin "2") (pinfunction "2_2") (pintype "input"))
      (node (ref "U7") (pin "34") (pinfunction "PA13_34") (pintype "input"))
    )
    (net (code "22") (name "M_D") (class "Default")
      (node (ref "R12") (pin "2") (pinfunction "2_2") (pintype "input"))
      (node (ref "U7") (pin "37") (pinfunction "PA14_37") (pintype "input"))
    )
    (net (code "23") (name "M_DIR") (class "Default")
      (node (ref "R16") (pin "1") (pinfunction "1_1") (pintype "input"))
      (node (ref "U11") (pin "2") (pinfunction "#RE_2") (pintype "input"))
      (node (ref "U11") (pin "3") (pinfunction "DE_3") (pintype "input"))
      (node (ref "U7") (pin "33") (pinfunction "PA12_33") (pintype "input"))
    )
    (net (code "24") (name "M_IO_PA4") (class "Default")
      (node (ref "H2") (pin "1") (pinfunction "1_1") (pintype "input"))
      (node (ref "U7") (pin "14") (pinfunction "PA4_14") (pintype "input"))
    )
    (net (code "25") (name "M_IO_PA5") (class "Default")
      (node (ref "H2") (pin "3") (pinfunction "3_3") (pintype "input"))
      (node (ref "U7") (pin "15") (pinfunction "PA5_15") (pintype "input"))
    )
    (net (code "26") (name "M_IO_PA6") (class "Default")
      (node (ref "H2") (pin "5") (pinfunction "5_5") (pintype "input"))
      (node (ref "U7") (pin "16") (pinfunction "PA6_16") (pintype "input"))
    )
    (net (code "27") (name "M_IO_PA7") (class "Default")
      (node (ref "H2") (pin "7") (pinfunction "7_7") (pintype "input"))
      (node (ref "U7") (pin "17") (pinfunction "PA7_17") (pintype "input"))
    )
    (net (code "28") (name "M_IO_PB1") (class "Default")
      (node (ref "H2") (pin "2") (pinfunction "2_2") (pintype "input"))
      (node (ref "U7") (pin "19") (pinfunction "PB1_19") (pintype "input"))
    )
    (net (code "29") (name "M_IO_PB2") (class "Default")
      (node (ref "H2") (pin "4") (pinfunction "4_4") (pintype "input"))
      (node (ref "U7") (pin "20") (pinfunction "PB2_20") (pintype "input"))
    )
    (net (code "30") (name "M_IO_PB10") (class "Default")
      (node (ref "H2") (pin "6") (pinfunction "6_6") (pintype "input"))
      (node (ref "U7") (pin "21") (pinfunction "PB10_21") (pintype "input"))
    )
    (net (code "31") (name "M_IO_PB11") (class "Default")
      (node (ref "H2") (pin "8") (pinfunction "8_8") (pintype "input"))
      (node (ref "U7") (pin "22") (pinfunction "PB11_22") (pintype "input"))
    )
    (net (code "32") (name "M_K1") (class "Default")
      (node (ref "U7") (pin "10") (pinfunction "PA0-WKUP_10") (pintype "input"))
      (node (ref "U9") (pin "1") (pinfunction "1B_1") (pintype "input"))
      (node (ref "U9") (pin "2") (pinfunction "2B_2") (pintype "input"))
    )
    (net (code "33") (name "M_K2") (class "Default")
      (node (ref "U7") (pin "11") (pinfunction "PA1_11") (pintype "input"))
      (node (ref "U9") (pin "3") (pinfunction "3B_3") (pintype "input"))
      (node (ref "U9") (pin "4") (pinfunction "4B_4") (pintype "input"))
    )
    (net (code "34") (name "M_K3") (class "Default")
      (node (ref "U7") (pin "12") (pinfunction "PA2_12") (pintype "input"))
      (node (ref "U9") (pin "5") (pinfunction "5B_5") (pintype "input"))
      (node (ref "U9") (pin "6") (pinfunction "6B_6") (pintype "input"))
    )
    (net (code "35") (name "M_K4") (class "Default")
      (node (ref "U7") (pin "13") (pinfunction "PA3_13") (pintype "input"))
      (node (ref "U9") (pin "7") (pinfunction "7B_7") (pintype "input"))
    )
    (net (code "36") (name "M_KC1") (class "Default")
      (node (ref "K1") (pin "2") (pinfunction "2_2") (pintype "input"))
      (node (ref "U9") (pin "15") (pinfunction "2C_15") (pintype "input"))
      (node (ref "U9") (pin "16") (pinfunction "1C_16") (pintype "input"))
    )
    (net (code "37") (name "M_KC2") (class "Default")
      (node (ref "K2") (pin "2") (pinfunction "2_2") (pintype "input"))
      (node (ref "U9") (pin "13") (pinfunction "4C_13") (pintype "input"))
      (node (ref "U9") (pin "14") (pinfunction "3C_14") (pintype "input"))
    )
    (net (code "38") (name "M_KC3") (class "Default")
      (node (ref "K3") (pin "2") (pinfunction "2_2") (pintype "input"))
      (node (ref "U9") (pin "11") (pinfunction "6C_11") (pintype "input"))
      (node (ref "U9") (pin "12") (pinfunction "5C_12") (pintype "input"))
    )
    (net (code "39") (name "M_KC4") (class "Default")
      (node (ref "K4") (pin "2") (pinfunction "2_2") (pintype "input"))
      (node (ref "U9") (pin "10") (pinfunction "7C_10") (pintype "input"))
    )
    (net (code "40") (name "M_RST#") (class "Default")
      (node (ref "C28") (pin "1") (pinfunction "1_1") (pintype "input"))
      (node (ref "R11") (pin "1") (pinfunction "1_1") (pintype "input"))
      (node (ref "U7") (pin "7") (pinfunction "NRST_7") (pintype "input"))
    )
    (net (code "41") (name "M_RXD") (class "Default")
      (node (ref "R18") (pin "2") (pinfunction "2_2") (pintype "input"))
      (node (ref "U11") (pin "1") (pinfunction "RO_1") (pintype "input"))
      (node (ref "U7") (pin "31") (pinfunction "PA10_31") (pintype "input"))
    )
    (net (code "42") (name "M_SCL") (class "Default")
      (node (ref "R15") (pin "2") (pinfunction "2_2") (pintype "input"))
      (node (ref "U10") (pin "6") (pinfunction "SCL_6") (pintype "input"))
      (node (ref "U7") (pin "42") (pinfunction "PB6_42") (pintype "input"))
    )
    (net (code "43") (name "M_SDA") (class "Default")
      (node (ref "R14") (pin "1") (pinfunction "1_1") (pintype "input"))
      (node (ref "U10") (pin "5") (pinfunction "SDA_5") (pintype "input"))
      (node (ref "U7") (pin "43") (pinfunction "PB7_43") (pintype "input"))
    )
    (net (code "44") (name "M_TXD") (class "Default")
      (node (ref "R17") (pin "1") (pinfunction "1_1") (pintype "input"))
      (node (ref "U11") (pin "4") (pinfunction "DI_4") (pintype "input"))
      (node (ref "U7") (pin "30") (pinfunction "PA9_30") (pintype "input"))
    )
    (net (code "45") (name "M_X1") (class "Default")
      (node (ref "C33") (pin "2") (pinfunction "2_2") (pintype "input"))
      (node (ref "U7") (pin "5") (pinfunction "PD0-OSCIN_5") (pintype "input"))
      (node (ref "U8") (pin "2") (pinfunction "2_2") (pintype "input"))
    )
    (net (code "46") (name "M_X2") (class "Default")
      (node (ref "C34") (pin "2") (pinfunction "2_2") (pintype "input"))
      (node (ref "U7") (pin "6") (pinfunction "PD1-OSCOUT_6") (pintype "input"))
      (node (ref "U8") (pin "1") (pinfunction "1_1") (pintype "input"))
    )
    (net (code "47") (name "Net-(H1-Pad1)") (class "Default")
      (node (ref "H1") (pin "1") (pinfunction "1_1") (pintype "input"))
      (node (ref "R12") (pin "1") (pinfunction "1_1") (pintype "input"))
    )
    (net (code "48") (name "Net-(H1-Pad4)") (class "Default")
      (node (ref "H1") (pin "4") (pinfunction "4_4") (pintype "input"))
      (node (ref "R13") (pin "1") (pinfunction "1_1") (pintype "input"))
    )
    (net (code "49") (name "Net-(J2-CHS_GND)") (class "Default")
      (node (ref "J2") (pin "8") (pinfunction "CHS_GND_8") (pintype "input"))
      (node (ref "R2") (pin "1") (pinfunction "1_1") (pintype "input"))
    )
    (net (code "50") (name "Net-(J2-Pad9)") (class "Default")
      (node (ref "J2") (pin "9") (pinfunction "9_9") (pintype "input"))
      (node (ref "R6") (pin "1") (pinfunction "1_1") (pintype "input"))
    )
    (net (code "51") (name "Net-(J2-Pad12)") (class "Default")
      (node (ref "J2") (pin "12") (pinfunction "12_12") (pintype "input"))
      (node (ref "R7") (pin "1") (pinfunction "1_1") (pintype "input"))
    )
    (net (code "52") (name "Net-(U1-RSETE)") (class "Default")
      (node (ref "R4") (pin "1") (pinfunction "1_1") (pintype "input"))
      (node (ref "U1") (pin "1") (pinfunction "RSETE_1") (pintype "input"))
    )
    (net (code "53") (name "Net-(U1-TXD)") (class "Default")
      (node (ref "R1") (pin "1") (pinfunction "1_1") (pintype "input"))
      (node (ref "U1") (pin "58") (pinfunction "TXD_58") (pintype "input"))
    )
    (net (code "54") (name "Net-(U11-A)") (class "Default")
      (node (ref "CN5") (pin "1") (pinfunction "1_1") (pintype "input"))
      (node (ref "R19") (pin "1") (pinfunction "1_1") (pintype "input"))
      (node (ref "R21") (pin "2") (pinfunction "2_2") (pintype "input"))
      (node (ref "U11") (pin "6") (pinfunction "A_6") (pintype "input"))
    )
    (net (code "55") (name "Net-(U11-B)") (class "Default")
      (node (ref "CN5") (pin "2") (pinfunction "2_2") (pintype "input"))
      (node (ref "R20") (pin "2") (pinfunction "2_2") (pintype "input"))
      (node (ref "R21") (pin "1") (pinfunction "1_1") (pintype "input"))
      (node (ref "U11") (pin "7") (pinfunction "B_7") (pintype "input"))
    )
    (net (code "56") (name "PGND") (class "Default")
      (node (ref "J2") (pin "SH1") (pinfunction "SH1_SH1") (pintype "input"))
      (node (ref "J2") (pin "SH2") (pinfunction "SH2_SH2") (pintype "input"))
      (node (ref "TP1") (pin "1") (pinfunction "1_1") (pintype "input"))
    )
    (net (code "57") (name "RXN") (class "Default")
      (node (ref "J2") (pin "6") (pinfunction "RD-_6") (pintype "input"))
      (node (ref "R3") (pin "1") (pinfunction "1_1") (pintype "input"))
      (node (ref "U1") (pin "5") (pinfunction "RXN_5") (pintype "input"))
    )
    (net (code "58") (name "RXP") (class "Default")
      (node (ref "J2") (pin "3") (pinfunction "RD+_3") (pintype "input"))
      (node (ref "R5") (pin "1") (pinfunction "1_1") (pintype "input"))
      (node (ref "U1") (pin "4") (pinfunction "RXP_4") (pintype "input"))
    )
    (net (code "59") (name "SEN_OUT") (class "Default")
      (node (ref "C39") (pin "1") (pinfunction "1_1") (pintype "input"))
      (node (ref "R22") (pin "1") (pinfunction "1_1") (pintype "input"))
      (node (ref "U12") (pin "4") (pinfunction "4_4") (pintype "input"))
      (node (ref "U7") (pin "18") (pinfunction "PB0_18") (pintype "input"))
    )
    (net (code "60") (name "S_CTRL") (class "Default")
      (node (ref "R23") (pin "2") (pinfunction "2_2") (pintype "input"))
      (node (ref "U13") (pin "4") (pinfunction "EN#_4") (pintype "input"))
      (node (ref "U7") (pin "38") (pinfunction "PA15_38") (pintype "input"))
    )
    (net (code "61") (name "TXN") (class "Default")
      (node (ref "J2") (pin "2") (pinfunction "TD-_2") (pintype "input"))
      (node (ref "R8") (pin "1") (pinfunction "1_1") (pintype "input"))
      (node (ref "U1") (pin "8") (pinfunction "TXN_8") (pintype "input"))
    )
    (net (code "62") (name "TXP") (class "Default")
      (node (ref "J2") (pin "1") (pinfunction "TD+_1") (pintype "input"))
      (node (ref "R9") (pin "1") (pinfunction "1_1") (pintype "input"))
      (node (ref "U1") (pin "7") (pinfunction "TXP_7") (pintype "input"))
    )
    (net (code "63") (name "V_HU") (class "Default")
      (node (ref "C40") (pin "2") (pinfunction "2_2") (pintype "input"))
      (node (ref "C42") (pin "2") (pinfunction "2_2") (pintype "input"))
      (node (ref "U12") (pin "1") (pinfunction "1_1") (pintype "input"))
      (node (ref "U13") (pin "1") (pinfunction "VOUT_1") (pintype "input"))
    )
    (net (code "64") (name "XI") (class "Default")
      (node (ref "C16") (pin "2") (pinfunction "2_2") (pintype "input"))
      (node (ref "U1") (pin "10") (pinfunction "XI_10") (pintype "input"))
      (node (ref "X1") (pin "2") (pinfunction "OSC2_2") (pintype "input"))
    )
    (net (code "65") (name "XO") (class "Default")
      (node (ref "C17") (pin "2") (pinfunction "2_2") (pintype "input"))
      (node (ref "U1") (pin "11") (pinfunction "XO_11") (pintype "input"))
      (node (ref "X1") (pin "1") (pinfunction "OSC1_1") (pintype "input"))
    )
    (net (code "66") (name "unconnected-(J2-NC-Pad7)") (class "Default")
      (node (ref "J2") (pin "7") (pinfunction "NC_7") (pintype "input+no_connect"))
    )
    (net (code "67") (name "unconnected-(OLED1-GND-Pad1)") (class "Default")
      (node (ref "OLED1") (pin "1") (pinfunction "GND_1") (pintype "input"))
    )
    (net (code "68") (name "unconnected-(OLED1-SCL-Pad3)") (class "Default")
      (node (ref "OLED1") (pin "3") (pinfunction "SCL_3") (pintype "input"))
    )
    (net (code "69") (name "unconnected-(OLED1-SDA-Pad4)") (class "Default")
      (node (ref "OLED1") (pin "4") (pinfunction "SDA_4") (pintype "input"))
    )
    (net (code "70") (name "unconnected-(OLED1-VCC-Pad2)") (class "Default")
      (node (ref "OLED1") (pin "2") (pinfunction "VCC_2") (pintype "input"))
    )
    (net (code "71") (name "unconnected-(U1-GPIO0-Pad22)") (class "Default")
      (node (ref "U1") (pin "22") (pinfunction "GPIO0_22") (pintype "input+no_connect"))
    )
    (net (code "72") (name "unconnected-(U1-GPIO1-Pad23)") (class "Default")
      (node (ref "U1") (pin "23") (pinfunction "GPIO1_23") (pintype "input+no_connect"))
    )
    (net (code "73") (name "unconnected-(U1-GPIO2-Pad24)") (class "Default")
      (node (ref "U1") (pin "24") (pinfunction "GPIO2_24") (pintype "input+no_connect"))
    )
    (net (code "74") (name "unconnected-(U1-GPIO4-Pad32)") (class "Default")
      (node (ref "U1") (pin "32") (pinfunction "GPIO4_32") (pintype "input+no_connect"))
    )
    (net (code "75") (name "unconnected-(U1-GPIO5-Pad33)") (class "Default")
      (node (ref "U1") (pin "33") (pinfunction "GPIO5_33") (pintype "input+no_connect"))
    )
    (net (code "76") (name "unconnected-(U1-GPIO6-Pad34)") (class "Default")
      (node (ref "U1") (pin "34") (pinfunction "GPIO6_34") (pintype "input+no_connect"))
    )
    (net (code "77") (name "unconnected-(U1-GPIO7-Pad35)") (class "Default")
      (node (ref "U1") (pin "35") (pinfunction "GPIO7_35") (pintype "input+no_connect"))
    )
    (net (code "78") (name "unconnected-(U1-NC-Pad14)") (class "Default")
      (node (ref "U1") (pin "14") (pinfunction "NC_14") (pintype "input+no_connect"))
    )
    (net (code "79") (name "unconnected-(U1-NC-Pad15)") (class "Default")
      (node (ref "U1") (pin "15") (pinfunction "NC_15") (pintype "input+no_connect"))
    )
    (net (code "80") (name "unconnected-(U1-NC-Pad16)") (class "Default")
      (node (ref "U1") (pin "16") (pinfunction "NC_16") (pintype "input+no_connect"))
    )
    (net (code "81") (name "unconnected-(U1-NC-Pad30)") (class "Default")
      (node (ref "U1") (pin "30") (pinfunction "NC_30") (pintype "input+no_connect"))
    )
    (net (code "82") (name "unconnected-(U1-NC-Pad31)") (class "Default")
      (node (ref "U1") (pin "31") (pinfunction "NC_31") (pintype "input+no_connect"))
    )
    (net (code "83") (name "unconnected-(U1-NC-Pad38)") (class "Default")
      (node (ref "U1") (pin "38") (pinfunction "NC_38") (pintype "input+no_connect"))
    )
    (net (code "84") (name "unconnected-(U1-NC-Pad39)") (class "Default")
      (node (ref "U1") (pin "39") (pinfunction "NC_39") (pintype "input+no_connect"))
    )
    (net (code "85") (name "unconnected-(U1-NC-Pad46)") (class "Default")
      (node (ref "U1") (pin "46") (pinfunction "NC_46") (pintype "input+no_connect"))
    )
    (net (code "86") (name "unconnected-(U1-NC-Pad47)") (class "Default")
      (node (ref "U1") (pin "47") (pinfunction "NC_47") (pintype "input+no_connect"))
    )
    (net (code "87") (name "unconnected-(U1-NC-Pad50)") (class "Default")
      (node (ref "U1") (pin "50") (pinfunction "NC_50") (pintype "input+no_connect"))
    )
    (net (code "88") (name "unconnected-(U1-NC-Pad51)") (class "Default")
      (node (ref "U1") (pin "51") (pinfunction "NC_51") (pintype "input+no_connect"))
    )
    (net (code "89") (name "unconnected-(U1-NC-Pad53)") (class "Default")
      (node (ref "U1") (pin "53") (pinfunction "NC_53") (pintype "input+no_connect"))
    )
    (net (code "90") (name "unconnected-(U1-NC-Pad55)") (class "Default")
      (node (ref "U1") (pin "55") (pinfunction "NC_55") (pintype "input+no_connect"))
    )
    (net (code "91") (name "unconnected-(U1-NC-Pad56)") (class "Default")
      (node (ref "U1") (pin "56") (pinfunction "NC_56") (pintype "input+no_connect"))
    )
    (net (code "92") (name "unconnected-(U1-RDY#GPIO3-Pad25)") (class "Default")
      (node (ref "U1") (pin "25") (pinfunction "RDY#GPIO3_25") (pintype "input+no_connect"))
    )
    (net (code "93") (name "unconnected-(U1-RST-Pad26)") (class "Default")
      (node (ref "U1") (pin "26") (pinfunction "RST_26") (pintype "input+no_connect"))
    )
    (net (code "94") (name "unconnected-(U1-RXD-Pad57)") (class "Default")
      (node (ref "U1") (pin "57") (pinfunction "RXD_57") (pintype "input+no_connect"))
    )
    (net (code "95") (name "unconnected-(U1-SEL-Pad27)") (class "Default")
      (node (ref "U1") (pin "27") (pinfunction "SEL_27") (pintype "input+no_connect"))
    )
    (net (code "96") (name "unconnected-(U7-PB3-Pad39)") (class "Default")
      (node (ref "U7") (pin "39") (pinfunction "PB3_39") (pintype "input+no_connect"))
    )
    (net (code "97") (name "unconnected-(U7-PB4-Pad40)") (class "Default")
      (node (ref "U7") (pin "40") (pinfunction "PB4_40") (pintype "input+no_connect"))
    )
    (net (code "98") (name "unconnected-(U7-PB5-Pad41)") (class "Default")
      (node (ref "U7") (pin "41") (pinfunction "PB5_41") (pintype "input+no_connect"))
    )
    (net (code "99") (name "unconnected-(U7-PB8-Pad45)") (class "Default")
      (node (ref "U7") (pin "45") (pinfunction "PB8_45") (pintype "input+no_connect"))
    )
    (net (code "100") (name "unconnected-(U7-PB9-Pad46)") (class "Default")
      (node (ref "U7") (pin "46") (pinfunction "PB9_46") (pintype "input+no_connect"))
    )
    (net (code "101") (name "unconnected-(U7-PC13-TAMPER-RTC-Pad2)") (class "Default")
      (node (ref "U7") (pin "2") (pinfunction "PC13-TAMPER-RTC_2") (pintype "input+no_connect"))
    )
    (net (code "102") (name "unconnected-(U7-PC14-OSC32IN-Pad3)") (class "Default")
      (node (ref "U7") (pin "3") (pinfunction "PC14-OSC32IN_3") (pintype "input+no_connect"))
    )
    (net (code "103") (name "unconnected-(U7-PC15-OSC32OUT-Pad4)") (class "Default")
      (node (ref "U7") (pin "4") (pinfunction "PC15-OSC32OUT_4") (pintype "input+no_connect"))
    )
    (net (code "104") (name "unconnected-(U13-FAULT-Pad5)") (class "Default")
      (node (ref "U13") (pin "5") (pinfunction "FAULT_5") (pintype "input+no_connect"))
    )
  )
)
